# MCPS_Power_030307.net
KiCad netlist of a schematic drawn in Altium Designer
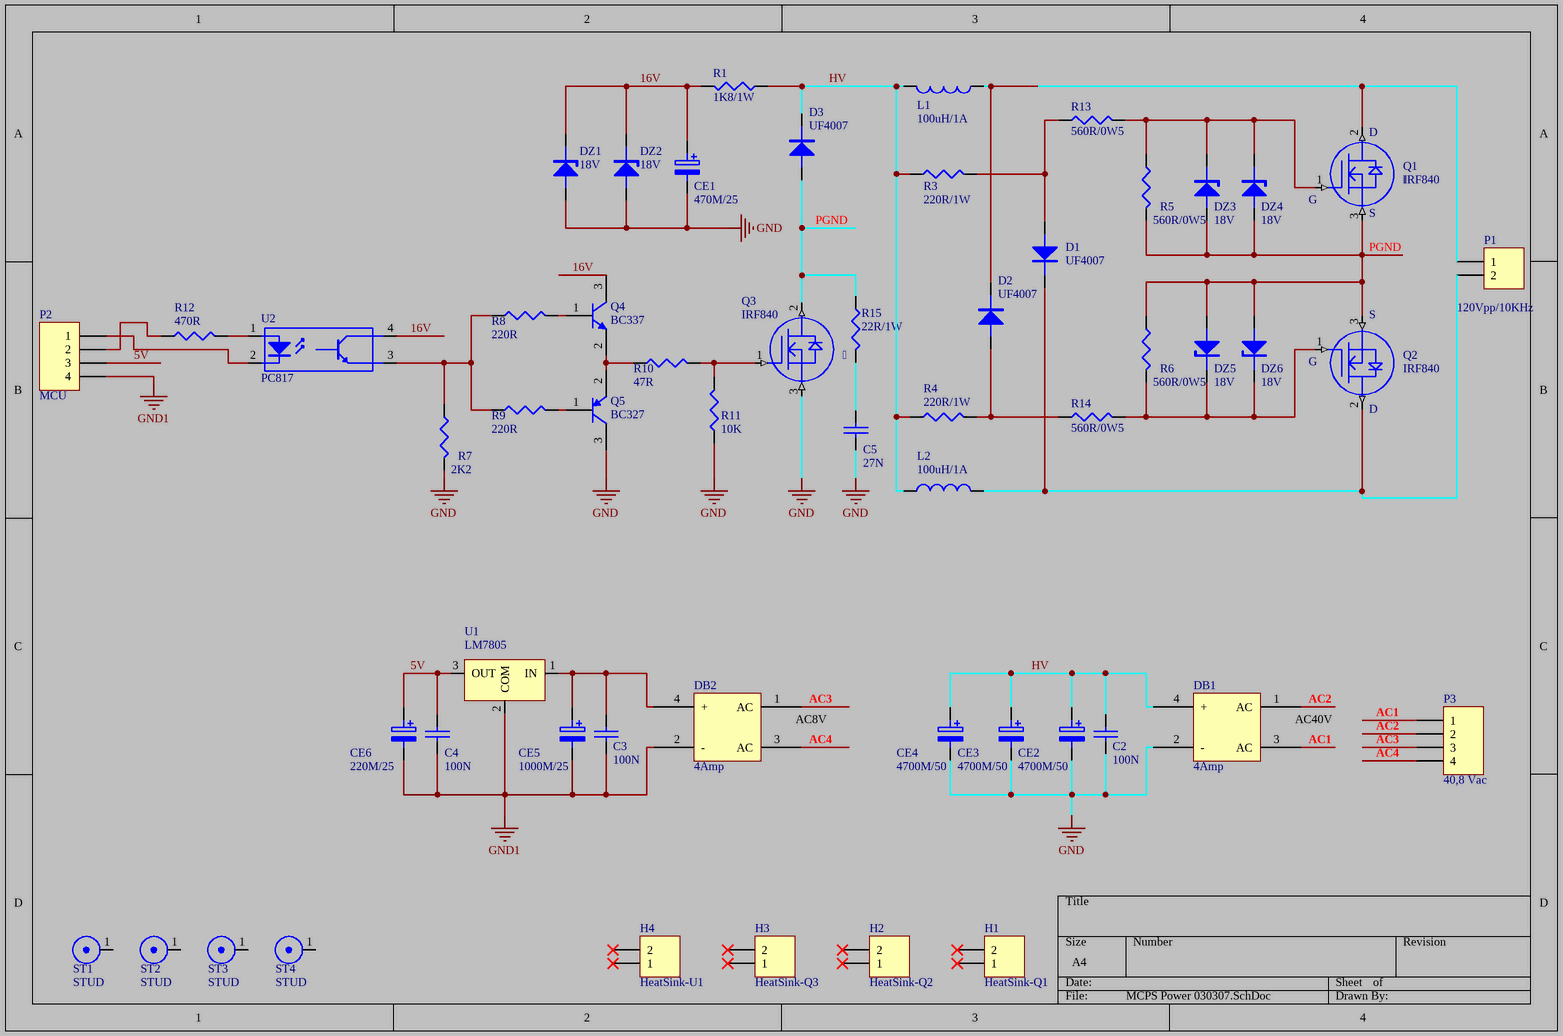
[diagram p0: MCPS Power 030307.SchDoc]

(export (version "E")
  (design (tool "Eeschema 10.0.6"))
  (components
    (comp (ref "C2") (value "100N") (footprint "c2P") (libsource (lib "*") (part "C")))
    (comp (ref "C3") (value "100N") (footprint "c2P") (libsource (lib "*") (part "C")))
    (comp (ref "C4") (value "100N") (footprint "c2P") (libsource (lib "*") (part "C")))
    (comp (ref "C5") (value "27N") (footprint "C5P") (libsource (lib "*") (part "C")))
    (comp (ref "CE1") (value "470M/25") (footprint "cap2p12") (libsource (lib "*") (part "E")))
    (comp (ref "CE2") (value "4700M/50") (footprint "CAP3P5") (libsource (lib "*") (part "E")))
    (comp (ref "CE3") (value "4700M/50") (footprint "CAP3P5") (libsource (lib "*") (part "E")))
    (comp (ref "CE4") (value "4700M/50") (footprint "CAP3P5") (libsource (lib "*") (part "E")))
    (comp (ref "CE5") (value "1000M/25") (footprint "cap2p12") (libsource (lib "*") (part "E")))
    (comp (ref "CE6") (value "220M/25") (footprint "cap2p12") (libsource (lib "*") (part "E")))
    (comp (ref "D1") (value "UF4007") (footprint "D4P") (libsource (lib "MyAltiumLib9702") (part "D")))
    (comp (ref "D2") (value "UF4007") (footprint "D4P") (libsource (lib "MyAltiumLib9702") (part "D")))
    (comp (ref "D3") (value "UF4007") (footprint "D4P") (libsource (lib "MyAltiumLib9702") (part "D")))
    (comp (ref "DB1")
      (value "4Amp")
      (footprint "BRG GBU")
      (libsource (lib "1402 Schlib 2020") (part "BRIDGE"))
    )
    (comp (ref "DB2") (value "4Amp") (footprint "BRG F") (libsource (lib "1402 Schlib 2020") (part "BRIDGE")))
    (comp (ref "DZ1") (value "18V") (footprint "D4P") (libsource (lib "MyAltiumLib9702") (part "DZ")))
    (comp (ref "DZ2") (value "18V") (footprint "D4P") (libsource (lib "MyAltiumLib9702") (part "DZ")))
    (comp (ref "DZ3") (value "18V") (footprint "D4P") (libsource (lib "MyAltiumLib9702") (part "DZ")))
    (comp (ref "DZ4") (value "18V") (footprint "D4P") (libsource (lib "MyAltiumLib9702") (part "DZ")))
    (comp (ref "DZ5") (value "18V") (footprint "D4P") (libsource (lib "MyAltiumLib9702") (part "DZ")))
    (comp (ref "DZ6") (value "18V") (footprint "D4P") (libsource (lib "MyAltiumLib9702") (part "DZ")))
    (comp (ref "H1")
      (value "HeatSink-Q1")
      (footprint "heatsink2")
      (description "Header, 2-Pin")
      (fields (field (name "PUBLISHER") "Altium Limited"))
      (libsource (lib "Miscellaneous Connectors") (part "Header 2"))
    )
    (comp (ref "H2")
      (value "HeatSink-Q2")
      (footprint "heatsink2")
      (description "Header, 2-Pin")
      (fields (field (name "PUBLISHER") "Altium Limited"))
      (libsource (lib "Miscellaneous Connectors") (part "Header 2"))
    )
    (comp (ref "H3")
      (value "HeatSink-Q3")
      (footprint "heatsink2")
      (description "Header, 2-Pin")
      (fields (field (name "PUBLISHER") "Altium Limited"))
      (libsource (lib "Miscellaneous Connectors") (part "Header 2"))
    )
    (comp (ref "H4")
      (value "HeatSink-U1")
      (footprint "heatsink5")
      (description "Header, 2-Pin")
      (fields (field (name "PUBLISHER") "Altium Limited"))
      (libsource (lib "Miscellaneous Connectors") (part "Header 2"))
    )
    (comp (ref "L1") (value "100uH/1A") (footprint "Inductor-Brown") (libsource (lib "") (part "INDUCTOR_1")))
    (comp (ref "L2")
      (value "100uH/1A")
      (footprint "Inductor-Brown")
      (libsource (lib "MyAltiumLib9702") (part "INDUCTOR"))
    )
    (comp (ref "P1")
      (value "120Vpp/10KHz")
      (footprint "2EDG")
      (description "Header, 2-Pin")
      (fields (field (name "PUBLISHER") "Altium Limited"))
      (libsource (lib "") (part "Header 2_1"))
    )
    (comp (ref "P2")
      (value "MCU")
      (footprint "DSIP4")
      (description "Header, 4-Pin")
      (fields (field (name "PUBLISHER") "Altium Limited"))
      (libsource (lib "") (part "Header 4_1"))
    )
    (comp (ref "P3")
      (value "40,8 Vac")
      (footprint "4EDG")
      (description "Header, 4-Pin")
      (fields (field (name "PUBLISHER") "Altium Limited"))
      (libsource (lib "Miscellaneous Connectors") (part "Header 4"))
    )
    (comp (ref "Q1") (value "") (footprint "TO220T") (libsource (lib "1402 Schlib 2020") (part "MOSFET N")))
    (comp (ref "Q2")
      (value "IRF840")
      (footprint "TO220T")
      (libsource (lib "1402 Schlib 2020") (part "MOSFET N"))
    )
    (comp (ref "Q3") (value "") (footprint "TO220T") (libsource (lib "1402 Schlib 2020") (part "MOSFET N")))
    (comp (ref "Q4")
      (value "BC337")
      (footprint "CBE-BC546")
      (libsource (lib "1402 Schlib 2020") (part "BC546"))
    )
    (comp (ref "Q5")
      (value "BC327")
      (footprint "CBE-BC546")
      (description "PNP")
      (fields (field (name "PUBLISHER") "Altium Limited"))
      (libsource (lib "1402 Schlib 2020") (part "M6"))
    )
    (comp (ref "R1") (value "1K8/1W") (footprint "w1") (libsource (lib "*") (part "R")))
    (comp (ref "R3") (value "220R/1W") (footprint "w1") (libsource (lib "*") (part "R")))
    (comp (ref "R4") (value "220R/1W") (footprint "w1") (libsource (lib "*") (part "R")))
    (comp (ref "R5") (value "560R/0W5") (footprint "R5P") (libsource (lib "*") (part "R")))
    (comp (ref "R6") (value "560R/0W5") (footprint "R5P") (libsource (lib "*") (part "R")))
    (comp (ref "R7") (value "2K2") (footprint "R4P") (libsource (lib "*") (part "R")))
    (comp (ref "R8") (value "220R") (footprint "R4P") (libsource (lib "*") (part "R")))
    (comp (ref "R9") (value "220R") (footprint "R4P") (libsource (lib "*") (part "R")))
    (comp (ref "R10") (value "47R") (footprint "R4P") (libsource (lib "*") (part "R")))
    (comp (ref "R11") (value "10K") (footprint "R4P") (libsource (lib "*") (part "R")))
    (comp (ref "R12") (value "470R") (footprint "R4P") (libsource (lib "*") (part "R")))
    (comp (ref "R13") (value "560R/0W5") (footprint "R5P") (libsource (lib "*") (part "R")))
    (comp (ref "R14") (value "560R/0W5") (footprint "R5P") (libsource (lib "*") (part "R")))
    (comp (ref "R15") (value "22R/1W") (footprint "w1") (libsource (lib "*") (part "R")))
    (comp (ref "ST1") (value "STUD") (footprint "CORNER") (libsource (lib "1402 Schlib 2020") (part "STUD")))
    (comp (ref "ST2") (value "STUD") (footprint "CORNER") (libsource (lib "1402 Schlib 2020") (part "STUD")))
    (comp (ref "ST3") (value "STUD") (footprint "CORNER") (libsource (lib "1402 Schlib 2020") (part "STUD")))
    (comp (ref "ST4") (value "STUD") (footprint "CORNER") (libsource (lib "1402 Schlib 2020") (part "STUD")))
    (comp (ref "U1")
      (value "LM7805")
      (footprint "TO220T")
      (description "SMD")
      (libsource (lib "1402 Schlib 2020") (part "Regulator"))
    )
    (comp (ref "U2")
      (value "PC817")
      (footprint "DIP4")
      (libsource (lib "1402 Schlib 2020") (part "OPTODIP4"))
    )
  )
  (nets
    (net (code "1") (name "/5V") (class "Default")
      (node (ref "C4") (pin "1") (pintype "passive"))
      (node (ref "CE6") (pin "1") (pintype "passive"))
      (node (ref "P2") (pin "3") (pinfunction "3_3") (pintype "passive"))
      (node (ref "U1") (pin "3") (pinfunction "OUT_3") (pintype "passive"))
    )
    (net (code "2") (name "/16V") (class "Default")
      (node (ref "CE1") (pin "1") (pintype "passive"))
      (node (ref "DZ1") (pin "2") (pinfunction "K_2") (pintype "passive"))
      (node (ref "DZ2") (pin "2") (pinfunction "K_2") (pintype "passive"))
      (node (ref "Q4") (pin "3") (pinfunction "C_3") (pintype "passive"))
      (node (ref "R1") (pin "2") (pintype "passive"))
      (node (ref "U2") (pin "4") (pinfunction "C_4") (pintype "passive"))
    )
    (net (code "3") (name "/AC1") (class "Default")
      (node (ref "DB1") (pin "3") (pinfunction "AC_3") (pintype "passive"))
      (node (ref "P3") (pin "1") (pinfunction "1_1") (pintype "passive"))
    )
    (net (code "4") (name "/AC2") (class "Default")
      (node (ref "DB1") (pin "1") (pinfunction "AC_1") (pintype "passive"))
      (node (ref "P3") (pin "2") (pinfunction "2_2") (pintype "passive"))
    )
    (net (code "5") (name "/AC3") (class "Default")
      (node (ref "DB2") (pin "1") (pinfunction "AC_1") (pintype "passive"))
      (node (ref "P3") (pin "3") (pinfunction "3_3") (pintype "passive"))
    )
    (net (code "6") (name "/AC4") (class "Default")
      (node (ref "DB2") (pin "3") (pinfunction "AC_3") (pintype "passive"))
      (node (ref "P3") (pin "4") (pinfunction "4_4") (pintype "passive"))
    )
    (net (code "7") (name "/HV") (class "Default")
      (node (ref "C2") (pin "1") (pintype "passive"))
      (node (ref "CE2") (pin "1") (pintype "passive"))
      (node (ref "CE3") (pin "1") (pintype "passive"))
      (node (ref "CE4") (pin "1") (pintype "passive"))
      (node (ref "D3") (pin "2") (pinfunction "K_2") (pintype "passive"))
      (node (ref "DB1") (pin "4") (pinfunction "+_4") (pintype "passive"))
      (node (ref "L1") (pin "1") (pinfunction "1_1") (pintype "passive"))
      (node (ref "L2") (pin "1") (pinfunction "1_1") (pintype "passive"))
      (node (ref "R1") (pin "1") (pintype "passive"))
      (node (ref "R3") (pin "1") (pintype "passive"))
      (node (ref "R4") (pin "1") (pintype "passive"))
    )
    (net (code "8") (name "/PGND") (class "Default")
      (node (ref "D3") (pin "1") (pinfunction "A_1") (pintype "passive"))
      (node (ref "DZ3") (pin "1") (pinfunction "A_1") (pintype "passive"))
      (node (ref "DZ4") (pin "1") (pinfunction "A_1") (pintype "passive"))
      (node (ref "DZ5") (pin "1") (pinfunction "A_1") (pintype "passive"))
      (node (ref "DZ6") (pin "1") (pinfunction "A_1") (pintype "passive"))
      (node (ref "Q1") (pin "3") (pinfunction "S_3") (pintype "input"))
      (node (ref "Q2") (pin "3") (pinfunction "S_3") (pintype "input"))
      (node (ref "Q3") (pin "2") (pinfunction "D_2") (pintype "output"))
      (node (ref "R15") (pin "1") (pintype "passive"))
      (node (ref "R5") (pin "2") (pintype "passive"))
      (node (ref "R6") (pin "1") (pintype "passive"))
    )
    (net (code "9") (name "GND") (class "Default")
      (node (ref "C2") (pin "2") (pintype "passive"))
      (node (ref "C5") (pin "2") (pintype "passive"))
      (node (ref "CE1") (pin "2") (pintype "passive"))
      (node (ref "CE2") (pin "2") (pintype "passive"))
      (node (ref "CE3") (pin "2") (pintype "passive"))
      (node (ref "CE4") (pin "2") (pintype "passive"))
      (node (ref "DB1") (pin "2") (pinfunction "-_2") (pintype "passive"))
      (node (ref "DZ1") (pin "1") (pinfunction "A_1") (pintype "passive"))
      (node (ref "DZ2") (pin "1") (pinfunction "A_1") (pintype "passive"))
      (node (ref "Q3") (pin "3") (pinfunction "S_3") (pintype "input"))
      (node (ref "Q5") (pin "3") (pinfunction "C_3") (pintype "passive"))
      (node (ref "R11") (pin "1") (pintype "passive"))
      (node (ref "R7") (pin "2") (pintype "passive"))
    )
    (net (code "10") (name "GND1") (class "Default")
      (node (ref "C3") (pin "2") (pintype "passive"))
      (node (ref "C4") (pin "2") (pintype "passive"))
      (node (ref "CE5") (pin "2") (pintype "passive"))
      (node (ref "CE6") (pin "2") (pintype "passive"))
      (node (ref "DB2") (pin "2") (pinfunction "-_2") (pintype "passive"))
      (node (ref "P2") (pin "4") (pinfunction "4_4") (pintype "passive"))
      (node (ref "U1") (pin "2") (pinfunction "COM_2") (pintype "passive"))
    )
    (net (code "11") (name "Net-(C5-Pad1)") (class "Default")
      (node (ref "C5") (pin "1") (pintype "passive"))
      (node (ref "R15") (pin "2") (pintype "passive"))
    )
    (net (code "12") (name "Net-(D1-A)") (class "Default")
      (node (ref "D1") (pin "1") (pinfunction "A_1") (pintype "passive"))
      (node (ref "R13") (pin "1") (pintype "passive"))
      (node (ref "R3") (pin "2") (pintype "passive"))
    )
    (net (code "13") (name "Net-(D1-K)") (class "Default")
      (node (ref "D1") (pin "2") (pinfunction "K_2") (pintype "passive"))
      (node (ref "L2") (pin "2") (pinfunction "2_2") (pintype "passive"))
      (node (ref "P1") (pin "2") (pinfunction "2_2") (pintype "passive"))
      (node (ref "Q2") (pin "2") (pinfunction "D_2") (pintype "output"))
    )
    (net (code "14") (name "Net-(D2-A)") (class "Default")
      (node (ref "D2") (pin "1") (pinfunction "A_1") (pintype "passive"))
      (node (ref "R14") (pin "1") (pintype "passive"))
      (node (ref "R4") (pin "2") (pintype "passive"))
    )
    (net (code "15") (name "Net-(D2-K)") (class "Default")
      (node (ref "D2") (pin "2") (pinfunction "K_2") (pintype "passive"))
      (node (ref "L1") (pin "2") (pinfunction "2_2") (pintype "passive"))
      (node (ref "P1") (pin "1") (pinfunction "1_1") (pintype "passive"))
      (node (ref "Q1") (pin "2") (pinfunction "D_2") (pintype "output"))
    )
    (net (code "16") (name "Net-(DB2-+)") (class "Default")
      (node (ref "C3") (pin "1") (pintype "passive"))
      (node (ref "CE5") (pin "1") (pintype "passive"))
      (node (ref "DB2") (pin "4") (pinfunction "+_4") (pintype "passive"))
      (node (ref "U1") (pin "1") (pinfunction "IN_1") (pintype "passive"))
    )
    (net (code "17") (name "Net-(DZ3-K)") (class "Default")
      (node (ref "DZ3") (pin "2") (pinfunction "K_2") (pintype "passive"))
      (node (ref "DZ4") (pin "2") (pinfunction "K_2") (pintype "passive"))
      (node (ref "Q1") (pin "1") (pinfunction "G_1") (pintype "input"))
      (node (ref "R13") (pin "2") (pintype "passive"))
      (node (ref "R5") (pin "1") (pintype "passive"))
    )
    (net (code "18") (name "Net-(DZ5-K)") (class "Default")
      (node (ref "DZ5") (pin "2") (pinfunction "K_2") (pintype "passive"))
      (node (ref "DZ6") (pin "2") (pinfunction "K_2") (pintype "passive"))
      (node (ref "Q2") (pin "1") (pinfunction "G_1") (pintype "input"))
      (node (ref "R14") (pin "2") (pintype "passive"))
      (node (ref "R6") (pin "2") (pintype "passive"))
    )
    (net (code "19") (name "Net-(P2-Pad2)") (class "Default")
      (node (ref "P2") (pin "2") (pinfunction "2_2") (pintype "passive"))
      (node (ref "R12") (pin "1") (pintype "passive"))
    )
    (net (code "20") (name "Net-(Q3-G)") (class "Default")
      (node (ref "Q3") (pin "1") (pinfunction "G_1") (pintype "input"))
      (node (ref "R10") (pin "2") (pintype "passive"))
      (node (ref "R11") (pin "2") (pintype "passive"))
    )
    (net (code "21") (name "Net-(Q4-B)") (class "Default")
      (node (ref "Q4") (pin "1") (pinfunction "B_1") (pintype "passive"))
      (node (ref "R8") (pin "2") (pintype "passive"))
    )
    (net (code "22") (name "Net-(Q4-E)") (class "Default")
      (node (ref "Q4") (pin "2") (pinfunction "E_2") (pintype "passive"))
      (node (ref "Q5") (pin "2") (pinfunction "B_2") (pintype "passive"))
      (node (ref "R10") (pin "1") (pintype "passive"))
    )
    (net (code "23") (name "Net-(Q5-E)") (class "Default")
      (node (ref "Q5") (pin "1") (pinfunction "E_1") (pintype "passive"))
      (node (ref "R9") (pin "2") (pintype "passive"))
    )
    (net (code "24") (name "Net-(U2-A)") (class "Default")
      (node (ref "R12") (pin "2") (pintype "passive"))
      (node (ref "U2") (pin "1") (pinfunction "A_1") (pintype "passive"))
    )
    (net (code "25") (name "Net-(U2-E)") (class "Default")
      (node (ref "R7") (pin "1") (pintype "passive"))
      (node (ref "R8") (pin "1") (pintype "passive"))
      (node (ref "R9") (pin "1") (pintype "passive"))
      (node (ref "U2") (pin "3") (pinfunction "E_3") (pintype "passive"))
    )
    (net (code "26") (name "Net-(U2-K)") (class "Default")
      (node (ref "P2") (pin "1") (pinfunction "1_1") (pintype "passive"))
      (node (ref "U2") (pin "2") (pinfunction "K_2") (pintype "passive"))
    )
    (net (code "27") (name "unconnected-(H1-Pad1)") (class "Default")
      (node (ref "H1") (pin "1") (pinfunction "1_1") (pintype "passive+no_connect"))
    )
    (net (code "28") (name "unconnected-(H1-Pad2)") (class "Default")
      (node (ref "H1") (pin "2") (pinfunction "2_2") (pintype "passive+no_connect"))
    )
    (net (code "29") (name "unconnected-(H2-Pad1)") (class "Default")
      (node (ref "H2") (pin "1") (pinfunction "1_1") (pintype "passive+no_connect"))
    )
    (net (code "30") (name "unconnected-(H2-Pad2)") (class "Default")
      (node (ref "H2") (pin "2") (pinfunction "2_2") (pintype "passive+no_connect"))
    )
    (net (code "31") (name "unconnected-(H3-Pad1)") (class "Default")
      (node (ref "H3") (pin "1") (pinfunction "1_1") (pintype "passive+no_connect"))
    )
    (net (code "32") (name "unconnected-(H3-Pad2)") (class "Default")
      (node (ref "H3") (pin "2") (pinfunction "2_2") (pintype "passive+no_connect"))
    )
    (net (code "33") (name "unconnected-(H4-Pad1)") (class "Default")
      (node (ref "H4") (pin "1") (pinfunction "1_1") (pintype "passive+no_connect"))
    )
    (net (code "34") (name "unconnected-(H4-Pad2)") (class "Default")
      (node (ref "H4") (pin "2") (pinfunction "2_2") (pintype "passive+no_connect"))
    )
    (net (code "35") (name "unconnected-(ST1-Pad1)") (class "Default")
      (node (ref "ST1") (pin "1") (pintype "passive"))
    )
    (net (code "36") (name "unconnected-(ST2-Pad1)") (class "Default")
      (node (ref "ST2") (pin "1") (pintype "passive"))
    )
    (net (code "37") (name "unconnected-(ST3-Pad1)") (class "Default")
      (node (ref "ST3") (pin "1") (pintype "passive"))
    )
    (net (code "38") (name "unconnected-(ST4-Pad1)") (class "Default")
      (node (ref "ST4") (pin "1") (pintype "passive"))
    )
  )
)
